# 32_pin_BB.net
KiCad netlist of a schematic drawn in EAGLE
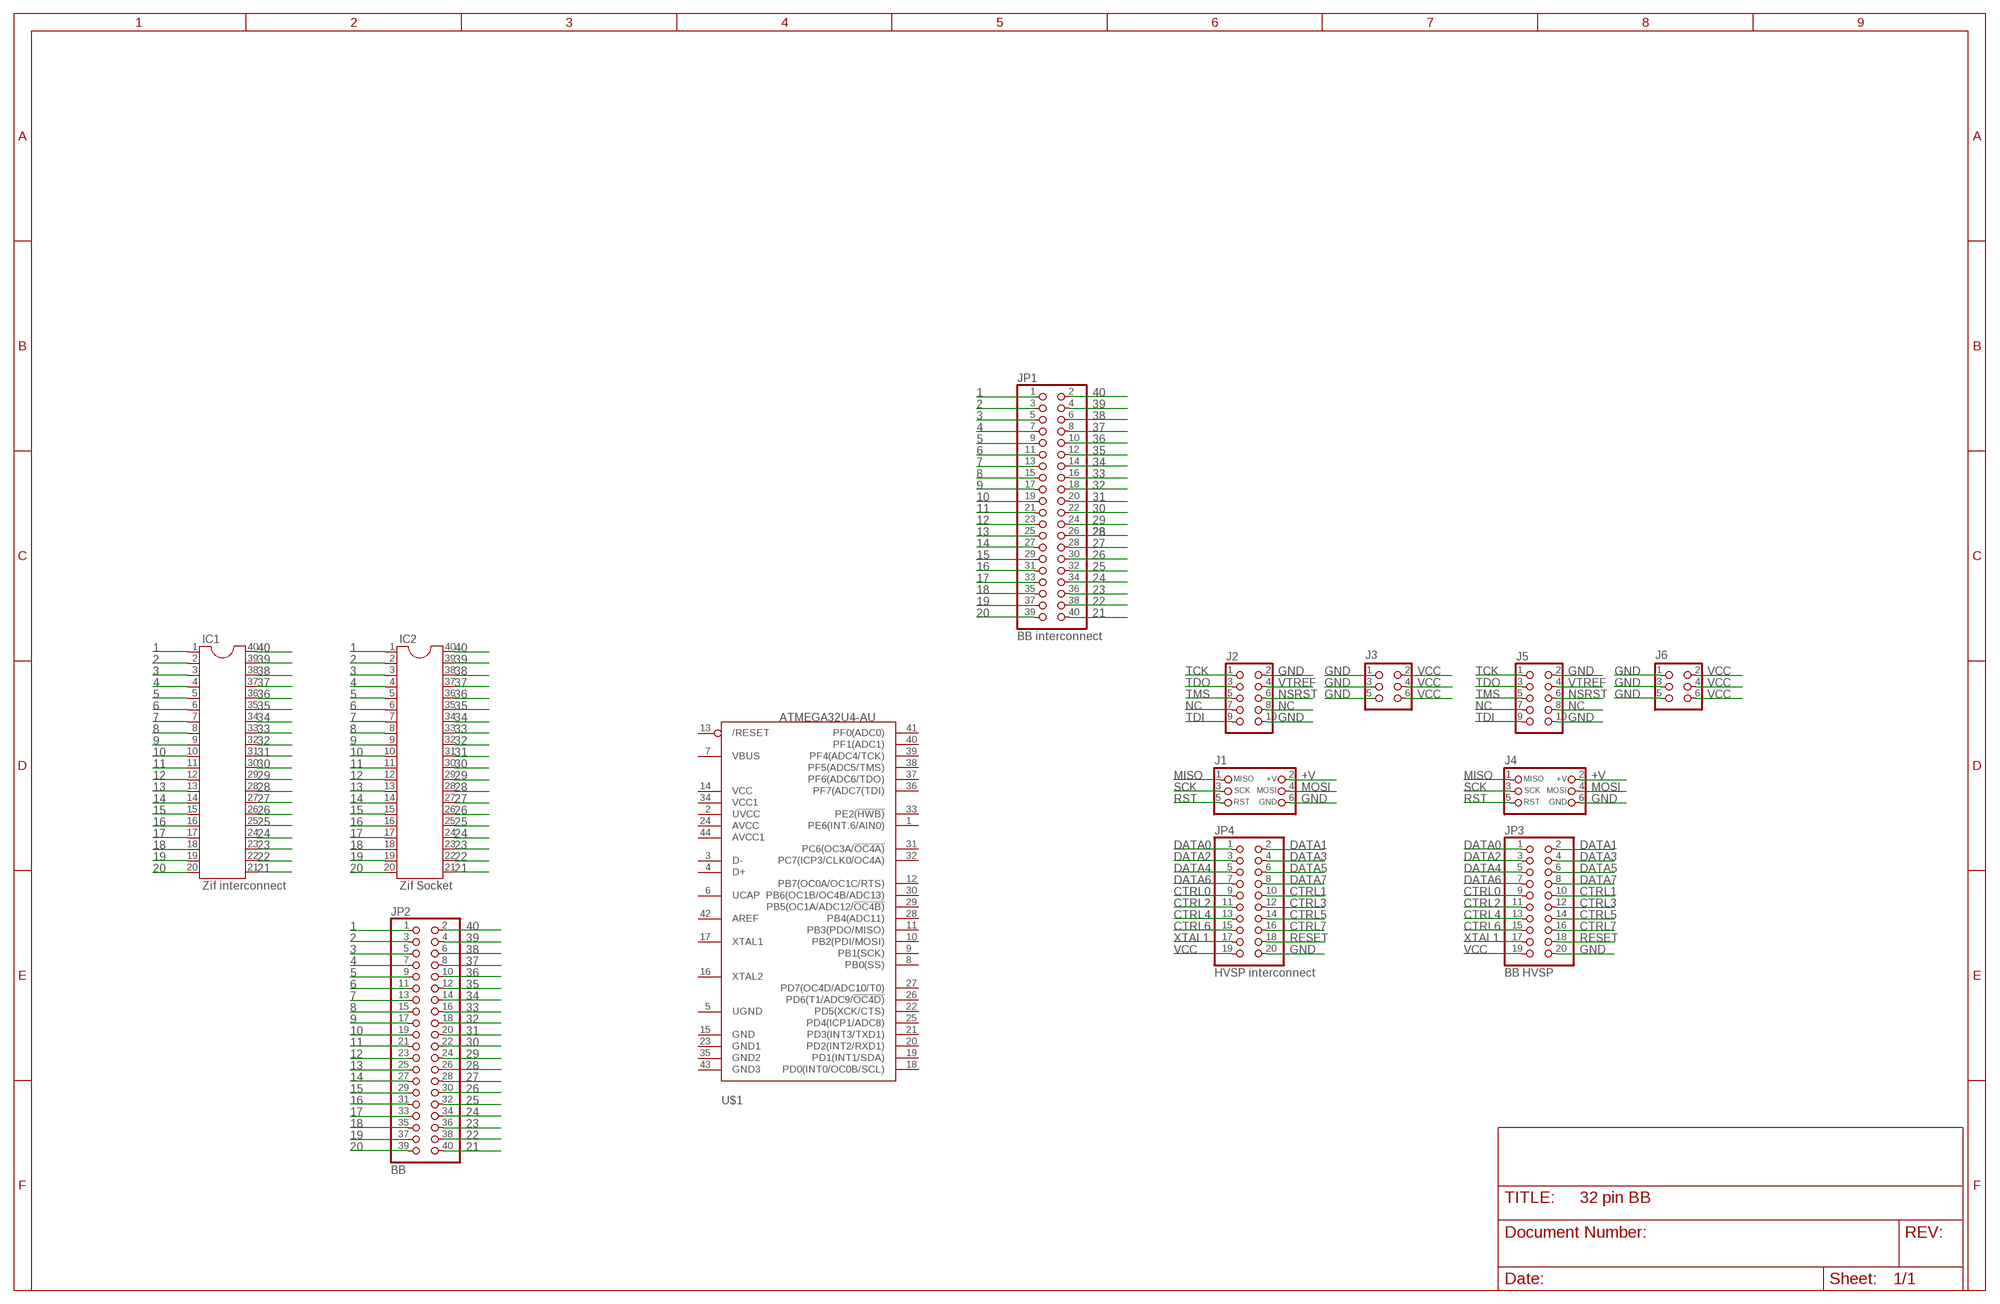
[diagram p0: schematic, sheet 1]

(export (version "E")
  (design (tool "Eeschema 10.0.6"))
  (components
    (comp (ref "IC1")
      (value "Zif interconnect")
      (footprint "eagle-import:DIL40")
      (libsource (lib "eagle-import") (part "DIL40"))
    )
    (comp (ref "IC2")
      (value "Zif Socket")
      (footprint "eagle-import:DIL40")
      (libsource (lib "eagle-import") (part "DIL40"))
    )
    (comp (ref "J1")
      (value "CON_HEADER_PRG_AVR_ICSP")
      (footprint "eagle-import:HEADER_PRG_2X03")
      (libsource (lib "eagle-import") (part "CON_HEADER_PRG_AVR_ICSP"))
    )
    (comp (ref "J2")
      (value "CON_HEADER_2X05-PTH")
      (footprint "eagle-import:M2X5")
      (libsource (lib "eagle-import") (part "CON_HEADER_2X05-PTH"))
    )
    (comp (ref "J3")
      (value "CON_HEADER_2X03-PTH")
      (footprint "eagle-import:M2X3")
      (libsource (lib "eagle-import") (part "CON_HEADER_2X03-PTH"))
    )
    (comp (ref "J4")
      (value "CON_HEADER_PRG_AVR_ICSP")
      (footprint "eagle-import:HEADER_PRG_2X03")
      (libsource (lib "eagle-import") (part "CON_HEADER_PRG_AVR_ICSP"))
    )
    (comp (ref "J5")
      (value "CON_HEADER_2X05-PTH")
      (footprint "eagle-import:M2X5")
      (libsource (lib "eagle-import") (part "CON_HEADER_2X05-PTH"))
    )
    (comp (ref "J6")
      (value "CON_HEADER_2X03-PTH")
      (footprint "eagle-import:M2X3")
      (libsource (lib "eagle-import") (part "CON_HEADER_2X03-PTH"))
    )
    (comp (ref "JP1")
      (value "BB interconnect")
      (footprint "eagle-import:2X20")
      (libsource (lib "eagle-import") (part "PINHD-2X20"))
    )
    (comp (ref "JP2")
      (value "BB")
      (footprint "eagle-import:2X20")
      (libsource (lib "eagle-import") (part "PINHD-2X20"))
    )
    (comp (ref "JP3")
      (value "BB HVSP")
      (footprint "eagle-import:2X10")
      (libsource (lib "eagle-import") (part "PINHD-2X10"))
    )
    (comp (ref "JP4")
      (value "HVSP interconnect")
      (footprint "eagle-import:2X10")
      (libsource (lib "eagle-import") (part "PINHD-2X10"))
    )
    (comp (ref "U$1")
      (value "ATMEGA32U4-AU")
      (footprint "eagle-import:TQFP44")
      (libsource (lib "eagle-import") (part "ATMEGA32U4-AU"))
    )
  )
  (nets
    (net (code "1") (name "/+V") (class "Default")
      (node (ref "J1") (pin "2") (pinfunction "+V_2") (pintype "passive"))
      (node (ref "J4") (pin "2") (pinfunction "+V_2") (pintype "passive"))
    )
    (net (code "2") (name "/1") (class "Default")
      (node (ref "IC1") (pin "1") (pinfunction "1_1") (pintype "passive"))
      (node (ref "IC2") (pin "1") (pinfunction "1_1") (pintype "passive"))
      (node (ref "JP1") (pin "1") (pinfunction "1_1") (pintype "passive"))
      (node (ref "JP2") (pin "1") (pinfunction "1_1") (pintype "passive"))
    )
    (net (code "3") (name "/2") (class "Default")
      (node (ref "IC1") (pin "2") (pinfunction "2_2") (pintype "passive"))
      (node (ref "IC2") (pin "2") (pinfunction "2_2") (pintype "passive"))
      (node (ref "JP1") (pin "3") (pinfunction "3_3") (pintype "passive"))
      (node (ref "JP2") (pin "3") (pinfunction "3_3") (pintype "passive"))
    )
    (net (code "4") (name "/3") (class "Default")
      (node (ref "IC1") (pin "3") (pinfunction "3_3") (pintype "passive"))
      (node (ref "IC2") (pin "3") (pinfunction "3_3") (pintype "passive"))
      (node (ref "JP1") (pin "5") (pinfunction "5_5") (pintype "passive"))
      (node (ref "JP2") (pin "5") (pinfunction "5_5") (pintype "passive"))
    )
    (net (code "5") (name "/4") (class "Default")
      (node (ref "IC1") (pin "4") (pinfunction "4_4") (pintype "passive"))
      (node (ref "IC2") (pin "4") (pinfunction "4_4") (pintype "passive"))
      (node (ref "JP1") (pin "7") (pinfunction "7_7") (pintype "passive"))
      (node (ref "JP2") (pin "7") (pinfunction "7_7") (pintype "passive"))
    )
    (net (code "6") (name "/5") (class "Default")
      (node (ref "IC1") (pin "5") (pinfunction "5_5") (pintype "passive"))
      (node (ref "IC2") (pin "5") (pinfunction "5_5") (pintype "passive"))
      (node (ref "JP1") (pin "9") (pinfunction "9_9") (pintype "passive"))
      (node (ref "JP2") (pin "9") (pinfunction "9_9") (pintype "passive"))
    )
    (net (code "7") (name "/6") (class "Default")
      (node (ref "IC1") (pin "6") (pinfunction "6_6") (pintype "passive"))
      (node (ref "IC2") (pin "6") (pinfunction "6_6") (pintype "passive"))
      (node (ref "JP1") (pin "11") (pinfunction "11_11") (pintype "passive"))
      (node (ref "JP2") (pin "11") (pinfunction "11_11") (pintype "passive"))
    )
    (net (code "8") (name "/7") (class "Default")
      (node (ref "IC1") (pin "7") (pinfunction "7_7") (pintype "passive"))
      (node (ref "IC2") (pin "7") (pinfunction "7_7") (pintype "passive"))
      (node (ref "JP1") (pin "13") (pinfunction "13_13") (pintype "passive"))
      (node (ref "JP2") (pin "13") (pinfunction "13_13") (pintype "passive"))
    )
    (net (code "9") (name "/8") (class "Default")
      (node (ref "IC1") (pin "8") (pinfunction "8_8") (pintype "passive"))
      (node (ref "IC2") (pin "8") (pinfunction "8_8") (pintype "passive"))
      (node (ref "JP1") (pin "15") (pinfunction "15_15") (pintype "passive"))
      (node (ref "JP2") (pin "15") (pinfunction "15_15") (pintype "passive"))
    )
    (net (code "10") (name "/9") (class "Default")
      (node (ref "IC1") (pin "9") (pinfunction "9_9") (pintype "passive"))
      (node (ref "IC2") (pin "9") (pinfunction "9_9") (pintype "passive"))
      (node (ref "JP1") (pin "17") (pinfunction "17_17") (pintype "passive"))
      (node (ref "JP2") (pin "17") (pinfunction "17_17") (pintype "passive"))
    )
    (net (code "11") (name "/10") (class "Default")
      (node (ref "IC1") (pin "10") (pinfunction "10_10") (pintype "passive"))
      (node (ref "IC2") (pin "10") (pinfunction "10_10") (pintype "passive"))
      (node (ref "JP1") (pin "19") (pinfunction "19_19") (pintype "passive"))
      (node (ref "JP2") (pin "19") (pinfunction "19_19") (pintype "passive"))
    )
    (net (code "12") (name "/11") (class "Default")
      (node (ref "IC1") (pin "11") (pinfunction "11_11") (pintype "passive"))
      (node (ref "IC2") (pin "11") (pinfunction "11_11") (pintype "passive"))
      (node (ref "JP1") (pin "21") (pinfunction "21_21") (pintype "passive"))
      (node (ref "JP2") (pin "21") (pinfunction "21_21") (pintype "passive"))
    )
    (net (code "13") (name "/12") (class "Default")
      (node (ref "IC1") (pin "12") (pinfunction "12_12") (pintype "passive"))
      (node (ref "IC2") (pin "12") (pinfunction "12_12") (pintype "passive"))
      (node (ref "JP1") (pin "23") (pinfunction "23_23") (pintype "passive"))
      (node (ref "JP2") (pin "23") (pinfunction "23_23") (pintype "passive"))
    )
    (net (code "14") (name "/13") (class "Default")
      (node (ref "IC1") (pin "13") (pinfunction "13_13") (pintype "passive"))
      (node (ref "IC2") (pin "13") (pinfunction "13_13") (pintype "passive"))
      (node (ref "JP1") (pin "25") (pinfunction "25_25") (pintype "passive"))
      (node (ref "JP2") (pin "25") (pinfunction "25_25") (pintype "passive"))
    )
    (net (code "15") (name "/14") (class "Default")
      (node (ref "IC1") (pin "14") (pinfunction "14_14") (pintype "passive"))
      (node (ref "IC2") (pin "14") (pinfunction "14_14") (pintype "passive"))
      (node (ref "JP1") (pin "27") (pinfunction "27_27") (pintype "passive"))
      (node (ref "JP2") (pin "27") (pinfunction "27_27") (pintype "passive"))
    )
    (net (code "16") (name "/15") (class "Default")
      (node (ref "IC1") (pin "15") (pinfunction "15_15") (pintype "passive"))
      (node (ref "IC2") (pin "15") (pinfunction "15_15") (pintype "passive"))
      (node (ref "JP1") (pin "29") (pinfunction "29_29") (pintype "passive"))
      (node (ref "JP2") (pin "29") (pinfunction "29_29") (pintype "passive"))
    )
    (net (code "17") (name "/16") (class "Default")
      (node (ref "IC1") (pin "16") (pinfunction "16_16") (pintype "passive"))
      (node (ref "IC2") (pin "16") (pinfunction "16_16") (pintype "passive"))
      (node (ref "JP1") (pin "31") (pinfunction "31_31") (pintype "passive"))
      (node (ref "JP2") (pin "31") (pinfunction "31_31") (pintype "passive"))
    )
    (net (code "18") (name "/17") (class "Default")
      (node (ref "IC1") (pin "17") (pinfunction "17_17") (pintype "passive"))
      (node (ref "IC2") (pin "17") (pinfunction "17_17") (pintype "passive"))
      (node (ref "JP1") (pin "33") (pinfunction "33_33") (pintype "passive"))
      (node (ref "JP2") (pin "33") (pinfunction "33_33") (pintype "passive"))
    )
    (net (code "19") (name "/18") (class "Default")
      (node (ref "IC1") (pin "18") (pinfunction "18_18") (pintype "passive"))
      (node (ref "IC2") (pin "18") (pinfunction "18_18") (pintype "passive"))
      (node (ref "JP1") (pin "35") (pinfunction "35_35") (pintype "passive"))
      (node (ref "JP2") (pin "35") (pinfunction "35_35") (pintype "passive"))
    )
    (net (code "20") (name "/19") (class "Default")
      (node (ref "IC1") (pin "19") (pinfunction "19_19") (pintype "passive"))
      (node (ref "IC2") (pin "19") (pinfunction "19_19") (pintype "passive"))
      (node (ref "JP1") (pin "37") (pinfunction "37_37") (pintype "passive"))
      (node (ref "JP2") (pin "37") (pinfunction "37_37") (pintype "passive"))
    )
    (net (code "21") (name "/20") (class "Default")
      (node (ref "IC1") (pin "20") (pinfunction "20_20") (pintype "passive"))
      (node (ref "IC2") (pin "20") (pinfunction "20_20") (pintype "passive"))
      (node (ref "JP1") (pin "39") (pinfunction "39_39") (pintype "passive"))
      (node (ref "JP2") (pin "39") (pinfunction "39_39") (pintype "passive"))
    )
    (net (code "22") (name "/21") (class "Default")
      (node (ref "IC1") (pin "21") (pinfunction "21_21") (pintype "passive"))
      (node (ref "IC2") (pin "21") (pinfunction "21_21") (pintype "passive"))
      (node (ref "JP1") (pin "40") (pinfunction "40_40") (pintype "passive"))
      (node (ref "JP2") (pin "40") (pinfunction "40_40") (pintype "passive"))
    )
    (net (code "23") (name "/22") (class "Default")
      (node (ref "IC1") (pin "22") (pinfunction "22_22") (pintype "passive"))
      (node (ref "IC2") (pin "22") (pinfunction "22_22") (pintype "passive"))
      (node (ref "JP1") (pin "38") (pinfunction "38_38") (pintype "passive"))
      (node (ref "JP2") (pin "38") (pinfunction "38_38") (pintype "passive"))
    )
    (net (code "24") (name "/23") (class "Default")
      (node (ref "IC1") (pin "23") (pinfunction "23_23") (pintype "passive"))
      (node (ref "IC2") (pin "23") (pinfunction "23_23") (pintype "passive"))
      (node (ref "JP1") (pin "36") (pinfunction "36_36") (pintype "passive"))
      (node (ref "JP2") (pin "36") (pinfunction "36_36") (pintype "passive"))
    )
    (net (code "25") (name "/24") (class "Default")
      (node (ref "IC1") (pin "24") (pinfunction "24_24") (pintype "passive"))
      (node (ref "IC2") (pin "24") (pinfunction "24_24") (pintype "passive"))
      (node (ref "JP1") (pin "34") (pinfunction "34_34") (pintype "passive"))
      (node (ref "JP2") (pin "34") (pinfunction "34_34") (pintype "passive"))
    )
    (net (code "26") (name "/25") (class "Default")
      (node (ref "IC1") (pin "25") (pinfunction "25_25") (pintype "passive"))
      (node (ref "IC2") (pin "25") (pinfunction "25_25") (pintype "passive"))
      (node (ref "JP1") (pin "32") (pinfunction "32_32") (pintype "passive"))
      (node (ref "JP2") (pin "32") (pinfunction "32_32") (pintype "passive"))
    )
    (net (code "27") (name "/26") (class "Default")
      (node (ref "IC1") (pin "26") (pinfunction "26_26") (pintype "passive"))
      (node (ref "IC2") (pin "26") (pinfunction "26_26") (pintype "passive"))
      (node (ref "JP1") (pin "30") (pinfunction "30_30") (pintype "passive"))
      (node (ref "JP2") (pin "30") (pinfunction "30_30") (pintype "passive"))
    )
    (net (code "28") (name "/27") (class "Default")
      (node (ref "IC1") (pin "27") (pinfunction "27_27") (pintype "passive"))
      (node (ref "IC2") (pin "27") (pinfunction "27_27") (pintype "passive"))
      (node (ref "JP1") (pin "28") (pinfunction "28_28") (pintype "passive"))
      (node (ref "JP2") (pin "28") (pinfunction "28_28") (pintype "passive"))
    )
    (net (code "29") (name "/28") (class "Default")
      (node (ref "IC1") (pin "28") (pinfunction "28_28") (pintype "passive"))
      (node (ref "IC2") (pin "28") (pinfunction "28_28") (pintype "passive"))
      (node (ref "JP1") (pin "26") (pinfunction "26_26") (pintype "passive"))
      (node (ref "JP2") (pin "26") (pinfunction "26_26") (pintype "passive"))
    )
    (net (code "30") (name "/29") (class "Default")
      (node (ref "IC1") (pin "29") (pinfunction "29_29") (pintype "passive"))
      (node (ref "IC2") (pin "29") (pinfunction "29_29") (pintype "passive"))
      (node (ref "JP1") (pin "24") (pinfunction "24_24") (pintype "passive"))
      (node (ref "JP2") (pin "24") (pinfunction "24_24") (pintype "passive"))
    )
    (net (code "31") (name "/30") (class "Default")
      (node (ref "IC1") (pin "30") (pinfunction "30_30") (pintype "passive"))
      (node (ref "IC2") (pin "30") (pinfunction "30_30") (pintype "passive"))
      (node (ref "JP1") (pin "22") (pinfunction "22_22") (pintype "passive"))
      (node (ref "JP2") (pin "22") (pinfunction "22_22") (pintype "passive"))
    )
    (net (code "32") (name "/31") (class "Default")
      (node (ref "IC1") (pin "31") (pinfunction "31_31") (pintype "passive"))
      (node (ref "IC2") (pin "31") (pinfunction "31_31") (pintype "passive"))
      (node (ref "JP1") (pin "20") (pinfunction "20_20") (pintype "passive"))
      (node (ref "JP2") (pin "20") (pinfunction "20_20") (pintype "passive"))
    )
    (net (code "33") (name "/32") (class "Default")
      (node (ref "IC1") (pin "32") (pinfunction "32_32") (pintype "passive"))
      (node (ref "IC2") (pin "32") (pinfunction "32_32") (pintype "passive"))
      (node (ref "JP1") (pin "18") (pinfunction "18_18") (pintype "passive"))
      (node (ref "JP2") (pin "18") (pinfunction "18_18") (pintype "passive"))
    )
    (net (code "34") (name "/33") (class "Default")
      (node (ref "IC1") (pin "33") (pinfunction "33_33") (pintype "passive"))
      (node (ref "IC2") (pin "33") (pinfunction "33_33") (pintype "passive"))
      (node (ref "JP1") (pin "16") (pinfunction "16_16") (pintype "passive"))
      (node (ref "JP2") (pin "16") (pinfunction "16_16") (pintype "passive"))
    )
    (net (code "35") (name "/34") (class "Default")
      (node (ref "IC1") (pin "34") (pinfunction "34_34") (pintype "passive"))
      (node (ref "IC2") (pin "34") (pinfunction "34_34") (pintype "passive"))
      (node (ref "JP1") (pin "14") (pinfunction "14_14") (pintype "passive"))
      (node (ref "JP2") (pin "14") (pinfunction "14_14") (pintype "passive"))
    )
    (net (code "36") (name "/35") (class "Default")
      (node (ref "IC1") (pin "35") (pinfunction "35_35") (pintype "passive"))
      (node (ref "IC2") (pin "35") (pinfunction "35_35") (pintype "passive"))
      (node (ref "JP1") (pin "12") (pinfunction "12_12") (pintype "passive"))
      (node (ref "JP2") (pin "12") (pinfunction "12_12") (pintype "passive"))
    )
    (net (code "37") (name "/36") (class "Default")
      (node (ref "IC1") (pin "36") (pinfunction "36_36") (pintype "passive"))
      (node (ref "IC2") (pin "36") (pinfunction "36_36") (pintype "passive"))
      (node (ref "JP1") (pin "10") (pinfunction "10_10") (pintype "passive"))
      (node (ref "JP2") (pin "10") (pinfunction "10_10") (pintype "passive"))
    )
    (net (code "38") (name "/37") (class "Default")
      (node (ref "IC1") (pin "37") (pinfunction "37_37") (pintype "passive"))
      (node (ref "IC2") (pin "37") (pinfunction "37_37") (pintype "passive"))
      (node (ref "JP1") (pin "8") (pinfunction "8_8") (pintype "passive"))
      (node (ref "JP2") (pin "8") (pinfunction "8_8") (pintype "passive"))
    )
    (net (code "39") (name "/38") (class "Default")
      (node (ref "IC1") (pin "38") (pinfunction "38_38") (pintype "passive"))
      (node (ref "IC2") (pin "38") (pinfunction "38_38") (pintype "passive"))
      (node (ref "JP1") (pin "6") (pinfunction "6_6") (pintype "passive"))
      (node (ref "JP2") (pin "6") (pinfunction "6_6") (pintype "passive"))
    )
    (net (code "40") (name "/39") (class "Default")
      (node (ref "IC1") (pin "39") (pinfunction "39_39") (pintype "passive"))
      (node (ref "IC2") (pin "39") (pinfunction "39_39") (pintype "passive"))
      (node (ref "JP1") (pin "4") (pinfunction "4_4") (pintype "passive"))
      (node (ref "JP2") (pin "4") (pinfunction "4_4") (pintype "passive"))
    )
    (net (code "41") (name "/40") (class "Default")
      (node (ref "IC1") (pin "40") (pinfunction "40_40") (pintype "passive"))
      (node (ref "IC2") (pin "40") (pinfunction "40_40") (pintype "passive"))
      (node (ref "JP1") (pin "2") (pinfunction "2_2") (pintype "passive"))
      (node (ref "JP2") (pin "2") (pinfunction "2_2") (pintype "passive"))
    )
    (net (code "42") (name "/CTRL0") (class "Default")
      (node (ref "JP3") (pin "9") (pinfunction "9_9") (pintype "passive"))
      (node (ref "JP4") (pin "9") (pinfunction "9_9") (pintype "passive"))
    )
    (net (code "43") (name "/CTRL1") (class "Default")
      (node (ref "JP3") (pin "10") (pinfunction "10_10") (pintype "passive"))
      (node (ref "JP4") (pin "10") (pinfunction "10_10") (pintype "passive"))
    )
    (net (code "44") (name "/CTRL2") (class "Default")
      (node (ref "JP3") (pin "11") (pinfunction "11_11") (pintype "passive"))
      (node (ref "JP4") (pin "11") (pinfunction "11_11") (pintype "passive"))
    )
    (net (code "45") (name "/CTRL3") (class "Default")
      (node (ref "JP3") (pin "12") (pinfunction "12_12") (pintype "passive"))
      (node (ref "JP4") (pin "12") (pinfunction "12_12") (pintype "passive"))
    )
    (net (code "46") (name "/CTRL4") (class "Default")
      (node (ref "JP3") (pin "13") (pinfunction "13_13") (pintype "passive"))
      (node (ref "JP4") (pin "13") (pinfunction "13_13") (pintype "passive"))
    )
    (net (code "47") (name "/CTRL5") (class "Default")
      (node (ref "JP3") (pin "14") (pinfunction "14_14") (pintype "passive"))
      (node (ref "JP4") (pin "14") (pinfunction "14_14") (pintype "passive"))
    )
    (net (code "48") (name "/CTRL6") (class "Default")
      (node (ref "JP3") (pin "15") (pinfunction "15_15") (pintype "passive"))
      (node (ref "JP4") (pin "15") (pinfunction "15_15") (pintype "passive"))
    )
    (net (code "49") (name "/CTRL7") (class "Default")
      (node (ref "JP3") (pin "16") (pinfunction "16_16") (pintype "passive"))
      (node (ref "JP4") (pin "16") (pinfunction "16_16") (pintype "passive"))
    )
    (net (code "50") (name "/DATA0") (class "Default")
      (node (ref "JP3") (pin "1") (pinfunction "1_1") (pintype "passive"))
      (node (ref "JP4") (pin "1") (pinfunction "1_1") (pintype "passive"))
    )
    (net (code "51") (name "/DATA1") (class "Default")
      (node (ref "JP3") (pin "2") (pinfunction "2_2") (pintype "passive"))
      (node (ref "JP4") (pin "2") (pinfunction "2_2") (pintype "passive"))
    )
    (net (code "52") (name "/DATA2") (class "Default")
      (node (ref "JP3") (pin "3") (pinfunction "3_3") (pintype "passive"))
      (node (ref "JP4") (pin "3") (pinfunction "3_3") (pintype "passive"))
    )
    (net (code "53") (name "/DATA3") (class "Default")
      (node (ref "JP3") (pin "4") (pinfunction "4_4") (pintype "passive"))
      (node (ref "JP4") (pin "4") (pinfunction "4_4") (pintype "passive"))
    )
    (net (code "54") (name "/DATA4") (class "Default")
      (node (ref "JP3") (pin "5") (pinfunction "5_5") (pintype "passive"))
      (node (ref "JP4") (pin "5") (pinfunction "5_5") (pintype "passive"))
    )
    (net (code "55") (name "/DATA5") (class "Default")
      (node (ref "JP3") (pin "6") (pinfunction "6_6") (pintype "passive"))
      (node (ref "JP4") (pin "6") (pinfunction "6_6") (pintype "passive"))
    )
    (net (code "56") (name "/DATA6") (class "Default")
      (node (ref "JP3") (pin "7") (pinfunction "7_7") (pintype "passive"))
      (node (ref "JP4") (pin "7") (pinfunction "7_7") (pintype "passive"))
    )
    (net (code "57") (name "/DATA7") (class "Default")
      (node (ref "JP3") (pin "8") (pinfunction "8_8") (pintype "passive"))
      (node (ref "JP4") (pin "8") (pinfunction "8_8") (pintype "passive"))
    )
    (net (code "58") (name "/GND") (class "Default")
      (node (ref "J1") (pin "6") (pinfunction "GND_6") (pintype "passive"))
      (node (ref "J2") (pin "10") (pinfunction "10_10") (pintype "passive"))
      (node (ref "J2") (pin "2") (pinfunction "2_2") (pintype "passive"))
      (node (ref "J3") (pin "1") (pinfunction "1_1") (pintype "passive"))
      (node (ref "J3") (pin "3") (pinfunction "3_3") (pintype "passive"))
      (node (ref "J3") (pin "5") (pinfunction "5_5") (pintype "passive"))
      (node (ref "J4") (pin "6") (pinfunction "GND_6") (pintype "passive"))
      (node (ref "J5") (pin "10") (pinfunction "10_10") (pintype "passive"))
      (node (ref "J5") (pin "2") (pinfunction "2_2") (pintype "passive"))
      (node (ref "J6") (pin "1") (pinfunction "1_1") (pintype "passive"))
      (node (ref "J6") (pin "3") (pinfunction "3_3") (pintype "passive"))
      (node (ref "J6") (pin "5") (pinfunction "5_5") (pintype "passive"))
      (node (ref "JP3") (pin "20") (pinfunction "20_20") (pintype "passive"))
      (node (ref "JP4") (pin "20") (pinfunction "20_20") (pintype "passive"))
    )
    (net (code "59") (name "/MISO") (class "Default")
      (node (ref "J1") (pin "1") (pinfunction "MISO_1") (pintype "passive"))
      (node (ref "J4") (pin "1") (pinfunction "MISO_1") (pintype "passive"))
    )
    (net (code "60") (name "/MOSI") (class "Default")
      (node (ref "J1") (pin "4") (pinfunction "MOSI_4") (pintype "passive"))
      (node (ref "J4") (pin "4") (pinfunction "MOSI_4") (pintype "passive"))
    )
    (net (code "61") (name "/NC") (class "Default")
      (node (ref "J2") (pin "7") (pinfunction "7_7") (pintype "passive"))
      (node (ref "J2") (pin "8") (pinfunction "8_8") (pintype "passive"))
      (node (ref "J5") (pin "7") (pinfunction "7_7") (pintype "passive"))
      (node (ref "J5") (pin "8") (pinfunction "8_8") (pintype "passive"))
    )
    (net (code "62") (name "/NSRST") (class "Default")
      (node (ref "J2") (pin "6") (pinfunction "6_6") (pintype "passive"))
      (node (ref "J5") (pin "6") (pinfunction "6_6") (pintype "passive"))
    )
    (net (code "63") (name "/RESET") (class "Default")
      (node (ref "JP3") (pin "18") (pinfunction "18_18") (pintype "passive"))
      (node (ref "JP4") (pin "18") (pinfunction "18_18") (pintype "passive"))
    )
    (net (code "64") (name "/RST") (class "Default")
      (node (ref "J1") (pin "5") (pinfunction "RST_5") (pintype "passive"))
      (node (ref "J4") (pin "5") (pinfunction "RST_5") (pintype "passive"))
    )
    (net (code "65") (name "/SCK") (class "Default")
      (node (ref "J1") (pin "3") (pinfunction "SCK_3") (pintype "passive"))
      (node (ref "J4") (pin "3") (pinfunction "SCK_3") (pintype "passive"))
    )
    (net (code "66") (name "/TCK") (class "Default")
      (node (ref "J2") (pin "1") (pinfunction "1_1") (pintype "passive"))
      (node (ref "J5") (pin "1") (pinfunction "1_1") (pintype "passive"))
    )
    (net (code "67") (name "/TDI") (class "Default")
      (node (ref "J2") (pin "9") (pinfunction "9_9") (pintype "passive"))
      (node (ref "J5") (pin "9") (pinfunction "9_9") (pintype "passive"))
    )
    (net (code "68") (name "/TDO") (class "Default")
      (node (ref "J2") (pin "3") (pinfunction "3_3") (pintype "passive"))
      (node (ref "J5") (pin "3") (pinfunction "3_3") (pintype "passive"))
    )
    (net (code "69") (name "/TMS") (class "Default")
      (node (ref "J2") (pin "5") (pinfunction "5_5") (pintype "passive"))
      (node (ref "J5") (pin "5") (pinfunction "5_5") (pintype "passive"))
    )
    (net (code "70") (name "/VCC") (class "Default")
      (node (ref "J3") (pin "2") (pinfunction "2_2") (pintype "passive"))
      (node (ref "J3") (pin "4") (pinfunction "4_4") (pintype "passive"))
      (node (ref "J3") (pin "6") (pinfunction "6_6") (pintype "passive"))
      (node (ref "J6") (pin "2") (pinfunction "2_2") (pintype "passive"))
      (node (ref "J6") (pin "4") (pinfunction "4_4") (pintype "passive"))
      (node (ref "J6") (pin "6") (pinfunction "6_6") (pintype "passive"))
      (node (ref "JP3") (pin "19") (pinfunction "19_19") (pintype "passive"))
      (node (ref "JP4") (pin "19") (pinfunction "19_19") (pintype "passive"))
    )
    (net (code "71") (name "/VTREF") (class "Default")
      (node (ref "J2") (pin "4") (pinfunction "4_4") (pintype "passive"))
      (node (ref "J5") (pin "4") (pinfunction "4_4") (pintype "passive"))
    )
    (net (code "72") (name "/XTAL1") (class "Default")
      (node (ref "JP3") (pin "17") (pinfunction "17_17") (pintype "passive"))
      (node (ref "JP4") (pin "17") (pinfunction "17_17") (pintype "passive"))
    )
    (net (code "73") (name "unconnected-(U$1-AREF-Pad42)") (class "Default")
      (node (ref "U$1") (pin "42") (pinfunction "AREF_42") (pintype "bidirectional"))
    )
    (net (code "74") (name "unconnected-(U$1-AVCC-Pad24)") (class "Default")
      (node (ref "U$1") (pin "24") (pinfunction "AVCC_24") (pintype "bidirectional"))
    )
    (net (code "75") (name "unconnected-(U$1-AVCC1-Pad44)") (class "Default")
      (node (ref "U$1") (pin "44") (pinfunction "AVCC1_44") (pintype "bidirectional"))
    )
    (net (code "76") (name "unconnected-(U$1-D+-Pad4)") (class "Default")
      (node (ref "U$1") (pin "4") (pinfunction "D+_4") (pintype "bidirectional"))
    )
    (net (code "77") (name "unconnected-(U$1-D--Pad3)") (class "Default")
      (node (ref "U$1") (pin "3") (pinfunction "D-_3") (pintype "bidirectional"))
    )
    (net (code "78") (name "unconnected-(U$1-GND-Pad15)") (class "Default")
      (node (ref "U$1") (pin "15") (pinfunction "GND_15") (pintype "bidirectional"))
    )
    (net (code "79") (name "unconnected-(U$1-GND1-Pad23)") (class "Default")
      (node (ref "U$1") (pin "23") (pinfunction "GND1_23") (pintype "bidirectional"))
    )
    (net (code "80") (name "unconnected-(U$1-GND2-Pad35)") (class "Default")
      (node (ref "U$1") (pin "35") (pinfunction "GND2_35") (pintype "bidirectional"))
    )
    (net (code "81") (name "unconnected-(U$1-GND3-Pad43)") (class "Default")
      (node (ref "U$1") (pin "43") (pinfunction "GND3_43") (pintype "bidirectional"))
    )
    (net (code "82") (name "unconnected-(U$1-PB0(SS)-Pad8)") (class "Default")
      (node (ref "U$1") (pin "8") (pinfunction "PB0(SS)_8") (pintype "bidirectional"))
    )
    (net (code "83") (name "unconnected-(U$1-PB1(SCK)-Pad9)") (class "Default")
      (node (ref "U$1") (pin "9") (pinfunction "PB1(SCK)_9") (pintype "bidirectional"))
    )
    (net (code "84") (name "unconnected-(U$1-PB2(PDI{slash}MOSI)-Pad10)") (class "Default")
      (node (ref "U$1") (pin "10") (pinfunction "PB2(PDI/MOSI)_10") (pintype "bidirectional"))
    )
    (net (code "85") (name "unconnected-(U$1-PB3(PDO{slash}MISO)-Pad11)") (class "Default")
      (node (ref "U$1") (pin "11") (pinfunction "PB3(PDO/MISO)_11") (pintype "bidirectional"))
    )
    (net (code "86") (name "unconnected-(U$1-PB4(ADC11)-Pad28)") (class "Default")
      (node (ref "U$1") (pin "28") (pinfunction "PB4(ADC11)_28") (pintype "bidirectional"))
    )
    (net (code "87") (name "unconnected-(U$1-PB5(OC1A{slash}ADC12{slash}~{OC4B})-Pad29)") (class "Default")
      (node (ref "U$1") (pin "29") (pinfunction "PB5(OC1A/ADC12/~{OC4B})_29") (pintype "bidirectional"))
    )
    (net (code "88") (name "unconnected-(U$1-PB6(OC1B{slash}OC4B{slash}ADC13)-Pad30)") (class "Default")
      (node (ref "U$1") (pin "30") (pinfunction "PB6(OC1B/OC4B/ADC13)_30") (pintype "bidirectional"))
    )
    (net (code "89") (name "unconnected-(U$1-PB7(OC0A{slash}OC1C{slash}RTS)-Pad12)") (class "Default")
      (node (ref "U$1") (pin "12") (pinfunction "PB7(OC0A/OC1C/RTS)_12") (pintype "bidirectional"))
    )
    (net (code "90") (name "unconnected-(U$1-PC6(OC3A{slash}~{OC4A})-Pad31)") (class "Default")
      (node (ref "U$1") (pin "31") (pinfunction "PC6(OC3A/~{OC4A})_31") (pintype "bidirectional"))
    )
    (net (code "91") (name "unconnected-(U$1-PC7(ICP3{slash}CLK0{slash}OC4A)-Pad32)") (class "Default")
      (node (ref "U$1") (pin "32") (pinfunction "PC7(ICP3/CLK0/OC4A)_32") (pintype "bidirectional"))
    )
    (net (code "92") (name "unconnected-(U$1-PD0(INT0{slash}OC0B{slash}SCL)-Pad18)") (class "Default")
      (node (ref "U$1") (pin "18") (pinfunction "PD0(INT0/OC0B/SCL)_18") (pintype "bidirectional"))
    )
    (net (code "93") (name "unconnected-(U$1-PD1(INT1{slash}SDA)-Pad19)") (class "Default")
      (node (ref "U$1") (pin "19") (pinfunction "PD1(INT1/SDA)_19") (pintype "bidirectional"))
    )
    (net (code "94") (name "unconnected-(U$1-PD2(INT2{slash}RXD1)-Pad20)") (class "Default")
      (node (ref "U$1") (pin "20") (pinfunction "PD2(INT2/RXD1)_20") (pintype "bidirectional"))
    )
    (net (code "95") (name "unconnected-(U$1-PD3(INT3{slash}TXD1)-Pad21)") (class "Default")
      (node (ref "U$1") (pin "21") (pinfunction "PD3(INT3/TXD1)_21") (pintype "bidirectional"))
    )
    (net (code "96") (name "unconnected-(U$1-PD4(ICP1{slash}ADC8)-Pad25)") (class "Default")
      (node (ref "U$1") (pin "25") (pinfunction "PD4(ICP1/ADC8)_25") (pintype "bidirectional"))
    )
    (net (code "97") (name "unconnected-(U$1-PD5(XCK{slash}CTS)-Pad22)") (class "Default")
      (node (ref "U$1") (pin "22") (pinfunction "PD5(XCK/CTS)_22") (pintype "bidirectional"))
    )
    (net (code "98") (name "unconnected-(U$1-PD6(T1{slash}ADC9{slash}~{OC4D})-Pad26)") (class "Default")
      (node (ref "U$1") (pin "26") (pinfunction "PD6(T1/ADC9/~{OC4D})_26") (pintype "bidirectional"))
    )
    (net (code "99") (name "unconnected-(U$1-PD7(OC4D{slash}ADC10{slash}T0)-Pad27)") (class "Default")
      (node (ref "U$1") (pin "27") (pinfunction "PD7(OC4D/ADC10/T0)_27") (pintype "bidirectional"))
    )
    (net (code "100") (name "unconnected-(U$1-PE2(~{HWB})-Pad33)") (class "Default")
      (node (ref "U$1") (pin "33") (pinfunction "PE2(~{HWB})_33") (pintype "bidirectional"))
    )
    (net (code "101") (name "unconnected-(U$1-PE6(INT.6{slash}AIN0)-Pad1)") (class "Default")
      (node (ref "U$1") (pin "1") (pinfunction "PE6(INT.6/AIN0)_1") (pintype "bidirectional"))
    )
    (net (code "102") (name "unconnected-(U$1-PF0(ADC0)-Pad41)") (class "Default")
      (node (ref "U$1") (pin "41") (pinfunction "PF0(ADC0)_41") (pintype "bidirectional"))
    )
    (net (code "103") (name "unconnected-(U$1-PF1(ADC1)-Pad40)") (class "Default")
      (node (ref "U$1") (pin "40") (pinfunction "PF1(ADC1)_40") (pintype "bidirectional"))
    )
    (net (code "104") (name "unconnected-(U$1-PF4(ADC4{slash}TCK)-Pad39)") (class "Default")
      (node (ref "U$1") (pin "39") (pinfunction "PF4(ADC4/TCK)_39") (pintype "bidirectional"))
    )
    (net (code "105") (name "unconnected-(U$1-PF5(ADC5{slash}TMS)-Pad38)") (class "Default")
      (node (ref "U$1") (pin "38") (pinfunction "PF5(ADC5/TMS)_38") (pintype "bidirectional"))
    )
    (net (code "106") (name "unconnected-(U$1-PF6(ADC6{slash}TDO)-Pad37)") (class "Default")
      (node (ref "U$1") (pin "37") (pinfunction "PF6(ADC6/TDO)_37") (pintype "bidirectional"))
    )
    (net (code "107") (name "unconnected-(U$1-PF7(ADC7(TDI)-Pad36)") (class "Default")
      (node (ref "U$1") (pin "36") (pinfunction "PF7(ADC7(TDI)_36") (pintype "bidirectional"))
    )
    (net (code "108") (name "unconnected-(U$1-UCAP-Pad6)") (class "Default")
      (node (ref "U$1") (pin "6") (pinfunction "UCAP_6") (pintype "bidirectional"))
    )
    (net (code "109") (name "unconnected-(U$1-UGND-Pad5)") (class "Default")
      (node (ref "U$1") (pin "5") (pinfunction "UGND_5") (pintype "bidirectional"))
    )
    (net (code "110") (name "unconnected-(U$1-UVCC-Pad2)") (class "Default")
      (node (ref "U$1") (pin "2") (pinfunction "UVCC_2") (pintype "bidirectional"))
    )
    (net (code "111") (name "unconnected-(U$1-VBUS-Pad7)") (class "Default")
      (node (ref "U$1") (pin "7") (pinfunction "VBUS_7") (pintype "bidirectional"))
    )
    (net (code "112") (name "unconnected-(U$1-VCC-Pad14)") (class "Default")
      (node (ref "U$1") (pin "14") (pinfunction "VCC_14") (pintype "bidirectional"))
    )
    (net (code "113") (name "unconnected-(U$1-VCC1-Pad34)") (class "Default")
      (node (ref "U$1") (pin "34") (pinfunction "VCC1_34") (pintype "bidirectional"))
    )
    (net (code "114") (name "unconnected-(U$1-XTAL1-Pad17)") (class "Default")
      (node (ref "U$1") (pin "17") (pinfunction "XTAL1_17") (pintype "bidirectional"))
    )
    (net (code "115") (name "unconnected-(U$1-XTAL2-Pad16)") (class "Default")
      (node (ref "U$1") (pin "16") (pinfunction "XTAL2_16") (pintype "bidirectional"))
    )
    (net (code "116") (name "unconnected-(U$1-{slash}RESET-Pad13)") (class "Default")
      (node (ref "U$1") (pin "13") (pinfunction "/RESET_13") (pintype "bidirectional"))
    )
  )
)
